# light_clock.net
KiCad netlist of a schematic drawn in Altium Designer
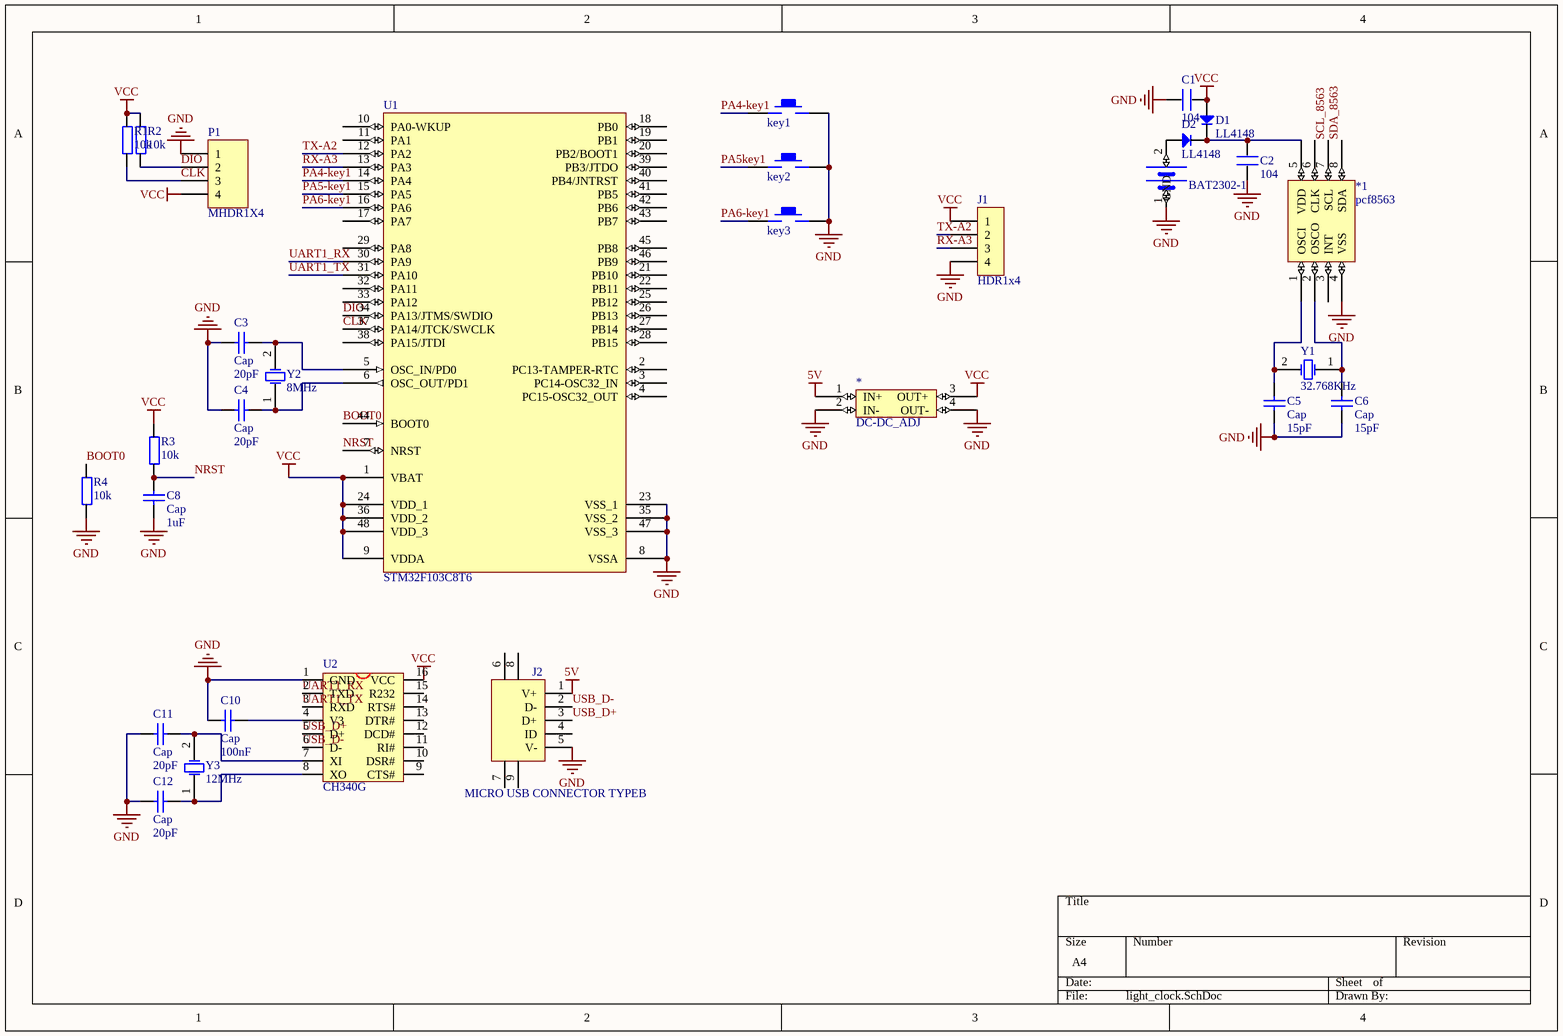
[diagram p0: light_clock.SchDoc]

(export (version "E")
  (design (tool "Eeschema 10.0.6"))
  (components
    (comp (ref "*")
      (value "DC-DC_ADJ")
      (footprint "DC-DC_ADJ")
      (libsource (lib "General") (part "DC-DC_ADJ"))
    )
    (comp (ref "*1") (value "pcf8563") (footprint "SOP-8") (libsource (lib "WARSHIP") (part "pcf8563")))
    (comp (ref "BAT2302-1")
      (value "BAT2302")
      (footprint "CR2302")
      (libsource (lib "WARSHIP") (part "BAT2302"))
    )
    (comp (ref "C1") (value "104") (footprint "0603") (libsource (lib "WARSHIP") (part "C")))
    (comp (ref "C2") (value "104") (footprint "0603") (libsource (lib "WARSHIP") (part "C")))
    (comp (ref "C3")
      (value "Cap")
      (footprint "0603")
      (description "Capacitor")
      (fields (field (name "ALTIUM_VALUE") "20pF") (field (name "PUBLISHER") "Altium Limited"))
      (libsource (lib "Miscellaneous Devices") (part "Cap"))
    )
    (comp (ref "C4")
      (value "Cap")
      (footprint "0603")
      (description "Capacitor")
      (fields (field (name "ALTIUM_VALUE") "20pF") (field (name "PUBLISHER") "Altium Limited"))
      (libsource (lib "Miscellaneous Devices") (part "Cap"))
    )
    (comp (ref "C5")
      (value "Cap")
      (footprint "0603")
      (description "Capacitor")
      (fields (field (name "ALTIUM_VALUE") "15pF") (field (name "PUBLISHER") "Altium Limited"))
      (libsource (lib "Miscellaneous Devices") (part "Cap"))
    )
    (comp (ref "C6")
      (value "Cap")
      (footprint "0603")
      (description "Capacitor")
      (fields (field (name "ALTIUM_VALUE") "15pF") (field (name "PUBLISHER") "Altium Limited"))
      (libsource (lib "Miscellaneous Devices") (part "Cap"))
    )
    (comp (ref "C8")
      (value "Cap")
      (footprint "0603")
      (description "Capacitor")
      (fields (field (name "ALTIUM_VALUE") "1uF") (field (name "PUBLISHER") "Altium Limited"))
      (libsource (lib "Miscellaneous Devices") (part "Cap"))
    )
    (comp (ref "C10")
      (value "Cap")
      (footprint "0603")
      (description "Capacitor")
      (fields (field (name "ALTIUM_VALUE") "100nF") (field (name "PUBLISHER") "Altium Limited"))
      (libsource (lib "Miscellaneous Devices") (part "Cap"))
    )
    (comp (ref "C11")
      (value "Cap")
      (footprint "0603")
      (description "Capacitor")
      (fields (field (name "ALTIUM_VALUE") "20pF") (field (name "PUBLISHER") "Altium Limited"))
      (libsource (lib "Miscellaneous Devices") (part "Cap"))
    )
    (comp (ref "C12")
      (value "Cap")
      (footprint "0603")
      (description "Capacitor")
      (fields (field (name "ALTIUM_VALUE") "20pF") (field (name "PUBLISHER") "Altium Limited"))
      (libsource (lib "Miscellaneous Devices") (part "Cap"))
    )
    (comp (ref "D1") (value "LL4148") (footprint "LL4148") (libsource (lib "WARSHIP") (part "LL4148")))
    (comp (ref "D2") (value "LL4148") (footprint "LL4148") (libsource (lib "WARSHIP") (part "LL4148")))
    (comp (ref "J1")
      (value "HDR1x4")
      (footprint "PIN-4-2.0-0.8")
      (description "Connector")
      (libsource (lib "General") (part "HDR1x4"))
    )
    (comp (ref "J2")
      (value "MICRO USB CONNECTOR TYPEB")
      (footprint "MICRO USB MK5P")
      (description "USB Connector")
      (libsource (lib "General") (part "MICRO USB CONNECTOR TYPEB"))
    )
    (comp (ref "key1") (value "KEY_M") (footprint "KEY_weidong") (libsource (lib "WARSHIP") (part "KEY_M")))
    (comp (ref "key2") (value "KEY_M") (footprint "KEY_weidong") (libsource (lib "WARSHIP") (part "KEY_M")))
    (comp (ref "key3") (value "KEY_M") (footprint "KEY_weidong") (libsource (lib "WARSHIP") (part "KEY_M")))
    (comp (ref "P1")
      (value "MHDR1X4")
      (footprint "HDR1X4")
      (description "Header, 4-Pin")
      (fields (field (name "PUBLISHER") "Altium Limited"))
      (libsource (lib "Miscellaneous Connectors") (part "MHDR1X4"))
    )
    (comp (ref "R1") (value "10k") (footprint "0603") (libsource (lib "WarShip V3 STM32103封装库") (part "R")))
    (comp (ref "R2") (value "10k") (footprint "0603") (libsource (lib "WarShip V3 STM32103封装库") (part "R")))
    (comp (ref "R3") (value "10k") (footprint "0603") (libsource (lib "WarShip V3 STM32103封装库") (part "R")))
    (comp (ref "R4") (value "10k") (footprint "0603") (libsource (lib "WarShip V3 STM32103封装库") (part "R")))
    (comp (ref "U1")
      (value "STM32F103C8T6")
      (footprint "STM-LQFP48_N")
      (description "STM32 ARM-based 32-bit MCU with 64 Kbytes Flash, 48-pin LQFP, Industrial Temperature")
      (fields (field (name "PUBLISHER") "*"))
      (libsource (lib "ST Microcontroller 32-Bit STM32 SCH") (part "STM32F103C8T6"))
    )
    (comp (ref "U2")
      (value "CH340G")
      (footprint "SOP16M")
      (description "USB2UART")
      (libsource (lib "WarShip V3 STM32103封装库") (part "CH340G"))
    )
    (comp (ref "Y1")
      (value "32.768KHz")
      (footprint "PIN-2-2.0-0.8")
      (description "Crystal Oscillator")
      (fields (field (name "PUBLISHER") "Altium Limited"))
      (libsource (lib "WarShip V3 STM32103封装库") (part "XTAL"))
    )
    (comp (ref "Y2")
      (value "8MHz")
      (footprint "XTAL_US")
      (description "Crystal Oscillator")
      (fields (field (name "PUBLISHER") "Altium Limited"))
      (libsource (lib "WarShip V3 STM32103封装库") (part "XTAL"))
    )
    (comp (ref "Y3")
      (value "12MHz")
      (footprint "PIN-2-2.0-0.8")
      (description "Crystal Oscillator")
      (fields (field (name "PUBLISHER") "Altium Limited"))
      (libsource (lib "WarShip V3 STM32103封装库") (part "XTAL"))
    )
  )
  (nets
    (net (code "1") (name "/BOOT0") (class "Default")
      (node (ref "R4") (pin "2") (pintype "passive"))
      (node (ref "U1") (pin "44") (pinfunction "BOOT0_44") (pintype "input"))
    )
    (net (code "2") (name "/CLK") (class "Default")
      (node (ref "P1") (pin "3") (pinfunction "3_3") (pintype "passive"))
      (node (ref "R1") (pin "1") (pintype "passive"))
      (node (ref "U1") (pin "37") (pinfunction "PA14/JTCK/SWCLK_37") (pintype "bidirectional"))
    )
    (net (code "3") (name "/DIO") (class "Default")
      (node (ref "P1") (pin "2") (pinfunction "2_2") (pintype "passive"))
      (node (ref "R2") (pin "1") (pintype "passive"))
      (node (ref "U1") (pin "34") (pinfunction "PA13/JTMS/SWDIO_34") (pintype "bidirectional"))
    )
    (net (code "4") (name "/NRST") (class "Default")
      (node (ref "C8") (pin "2") (pinfunction "2_2") (pintype "passive"))
      (node (ref "R3") (pin "1") (pintype "passive"))
      (node (ref "U1") (pin "7") (pinfunction "NRST_7") (pintype "bidirectional"))
    )
    (net (code "5") (name "/PA4-key1") (class "Default")
      (node (ref "U1") (pin "14") (pinfunction "PA4_14") (pintype "bidirectional"))
      (node (ref "key1") (pin "1") (pinfunction "1_1") (pintype "passive"))
    )
    (net (code "6") (name "/PA5-key1") (class "Default")
      (node (ref "U1") (pin "15") (pinfunction "PA5_15") (pintype "bidirectional"))
    )
    (net (code "7") (name "/PA5key1") (class "Default")
      (node (ref "key2") (pin "1") (pinfunction "1_1") (pintype "passive"))
    )
    (net (code "8") (name "/PA6-key1") (class "Default")
      (node (ref "U1") (pin "16") (pinfunction "PA6_16") (pintype "bidirectional"))
      (node (ref "key3") (pin "1") (pinfunction "1_1") (pintype "passive"))
    )
    (net (code "9") (name "/RX-A3") (class "Default")
      (node (ref "J1") (pin "3") (pinfunction "3_3") (pintype "passive"))
      (node (ref "U1") (pin "13") (pinfunction "PA3_13") (pintype "bidirectional"))
    )
    (net (code "10") (name "/SCL_8563") (class "Default")
      (node (ref "*1") (pin "7") (pinfunction "SCL_7") (pintype "bidirectional"))
    )
    (net (code "11") (name "/SDA_8563") (class "Default")
      (node (ref "*1") (pin "8") (pinfunction "SDA_8") (pintype "bidirectional"))
    )
    (net (code "12") (name "/TX-A2") (class "Default")
      (node (ref "J1") (pin "2") (pinfunction "2_2") (pintype "passive"))
      (node (ref "U1") (pin "12") (pinfunction "PA2_12") (pintype "bidirectional"))
    )
    (net (code "13") (name "/UART1_RX") (class "Default")
      (node (ref "U1") (pin "30") (pinfunction "PA9_30") (pintype "bidirectional"))
      (node (ref "U2") (pin "2") (pinfunction "TXD_2") (pintype "passive"))
    )
    (net (code "14") (name "/UART1_TX") (class "Default")
      (node (ref "U1") (pin "31") (pinfunction "PA10_31") (pintype "bidirectional"))
      (node (ref "U2") (pin "3") (pinfunction "RXD_3") (pintype "passive"))
    )
    (net (code "15") (name "/USB_D+") (class "Default")
      (node (ref "J2") (pin "3") (pinfunction "D+_3") (pintype "passive"))
      (node (ref "U2") (pin "5") (pinfunction "D+_5") (pintype "passive"))
    )
    (net (code "16") (name "/USB_D-") (class "Default")
      (node (ref "J2") (pin "2") (pinfunction "D-_2") (pintype "passive"))
      (node (ref "U2") (pin "6") (pinfunction "D-_6") (pintype "passive"))
    )
    (net (code "17") (name "5V") (class "Default")
      (node (ref "*") (pin "1") (pinfunction "IN+_1") (pintype "bidirectional"))
      (node (ref "J2") (pin "1") (pinfunction "V+_1") (pintype "passive"))
    )
    (net (code "18") (name "GND") (class "Default")
      (node (ref "*") (pin "2") (pinfunction "IN-_2") (pintype "bidirectional"))
      (node (ref "*") (pin "4") (pinfunction "OUT-_4") (pintype "bidirectional"))
      (node (ref "*1") (pin "4") (pinfunction "VSS_4") (pintype "bidirectional"))
      (node (ref "BAT2302-1") (pin "1") (pinfunction "VCC_1") (pintype "bidirectional"))
      (node (ref "C1") (pin "1") (pintype "passive"))
      (node (ref "C10") (pin "2") (pinfunction "2_2") (pintype "passive"))
      (node (ref "C11") (pin "1") (pinfunction "1_1") (pintype "passive"))
      (node (ref "C12") (pin "1") (pinfunction "1_1") (pintype "passive"))
      (node (ref "C2") (pin "1") (pintype "passive"))
      (node (ref "C3") (pin "1") (pinfunction "1_1") (pintype "passive"))
      (node (ref "C4") (pin "1") (pinfunction "1_1") (pintype "passive"))
      (node (ref "C5") (pin "1") (pinfunction "1_1") (pintype "passive"))
      (node (ref "C6") (pin "1") (pinfunction "1_1") (pintype "passive"))
      (node (ref "C8") (pin "1") (pinfunction "1_1") (pintype "passive"))
      (node (ref "J1") (pin "4") (pinfunction "4_4") (pintype "passive"))
      (node (ref "J2") (pin "5") (pinfunction "V-_5") (pintype "passive"))
      (node (ref "P1") (pin "1") (pinfunction "1_1") (pintype "passive"))
      (node (ref "R4") (pin "1") (pintype "passive"))
      (node (ref "U1") (pin "23") (pinfunction "VSS_1_23") (pintype "power_in"))
      (node (ref "U1") (pin "35") (pinfunction "VSS_2_35") (pintype "power_in"))
      (node (ref "U1") (pin "47") (pinfunction "VSS_3_47") (pintype "power_in"))
      (node (ref "U1") (pin "8") (pinfunction "VSSA_8") (pintype "power_in"))
      (node (ref "U2") (pin "1") (pinfunction "GND_1") (pintype "passive"))
      (node (ref "key1") (pin "2") (pinfunction "2_2") (pintype "passive"))
      (node (ref "key2") (pin "2") (pinfunction "2_2") (pintype "passive"))
      (node (ref "key3") (pin "2") (pinfunction "2_2") (pintype "passive"))
    )
    (net (code "19") (name "Net-(*1-OSCI)") (class "Default")
      (node (ref "*1") (pin "1") (pinfunction "OSCI_1") (pintype "bidirectional"))
      (node (ref "C5") (pin "2") (pinfunction "2_2") (pintype "passive"))
      (node (ref "Y1") (pin "2") (pinfunction "OSC2_2") (pintype "passive"))
    )
    (net (code "20") (name "Net-(*1-OSCO)") (class "Default")
      (node (ref "*1") (pin "2") (pinfunction "OSCO_2") (pintype "bidirectional"))
      (node (ref "C6") (pin "2") (pinfunction "2_2") (pintype "passive"))
      (node (ref "Y1") (pin "1") (pinfunction "OSC1_1") (pintype "passive"))
    )
    (net (code "21") (name "Net-(*1-VDD)") (class "Default")
      (node (ref "*1") (pin "5") (pinfunction "VDD_5") (pintype "bidirectional"))
      (node (ref "C2") (pin "2") (pintype "passive"))
      (node (ref "D1") (pin "1") (pintype "passive"))
      (node (ref "D2") (pin "1") (pintype "passive"))
    )
    (net (code "22") (name "Net-(BAT2302-1-GND)") (class "Default")
      (node (ref "BAT2302-1") (pin "2") (pinfunction "GND_2") (pintype "bidirectional"))
      (node (ref "D2") (pin "2") (pintype "passive"))
    )
    (net (code "23") (name "Net-(U1-OSC_IN{slash}PD0)") (class "Default")
      (node (ref "C3") (pin "2") (pinfunction "2_2") (pintype "passive"))
      (node (ref "U1") (pin "5") (pinfunction "OSC_IN/PD0_5") (pintype "input"))
      (node (ref "Y2") (pin "2") (pinfunction "OSC2_2") (pintype "passive"))
    )
    (net (code "24") (name "Net-(U1-OSC_OUT{slash}PD1)") (class "Default")
      (node (ref "C4") (pin "2") (pinfunction "2_2") (pintype "passive"))
      (node (ref "U1") (pin "6") (pinfunction "OSC_OUT/PD1_6") (pintype "output"))
      (node (ref "Y2") (pin "1") (pinfunction "OSC1_1") (pintype "passive"))
    )
    (net (code "25") (name "Net-(U2-V3)") (class "Default")
      (node (ref "C10") (pin "1") (pinfunction "1_1") (pintype "passive"))
      (node (ref "U2") (pin "4") (pinfunction "V3_4") (pintype "passive"))
    )
    (net (code "26") (name "Net-(U2-XI)") (class "Default")
      (node (ref "C11") (pin "2") (pinfunction "2_2") (pintype "passive"))
      (node (ref "U2") (pin "7") (pinfunction "XI_7") (pintype "passive"))
      (node (ref "Y3") (pin "2") (pinfunction "OSC2_2") (pintype "passive"))
    )
    (net (code "27") (name "Net-(U2-XO)") (class "Default")
      (node (ref "C12") (pin "2") (pinfunction "2_2") (pintype "passive"))
      (node (ref "U2") (pin "8") (pinfunction "XO_8") (pintype "passive"))
      (node (ref "Y3") (pin "1") (pinfunction "OSC1_1") (pintype "passive"))
    )
    (net (code "28") (name "VCC") (class "Default")
      (node (ref "*") (pin "3") (pinfunction "OUT+_3") (pintype "bidirectional"))
      (node (ref "C1") (pin "2") (pintype "passive"))
      (node (ref "D1") (pin "2") (pintype "passive"))
      (node (ref "J1") (pin "1") (pinfunction "1_1") (pintype "passive"))
      (node (ref "P1") (pin "4") (pinfunction "4_4") (pintype "passive"))
      (node (ref "R1") (pin "2") (pintype "passive"))
      (node (ref "R2") (pin "2") (pintype "passive"))
      (node (ref "R3") (pin "2") (pintype "passive"))
      (node (ref "U1") (pin "1") (pinfunction "VBAT_1") (pintype "power_in"))
      (node (ref "U1") (pin "24") (pinfunction "VDD_1_24") (pintype "power_in"))
      (node (ref "U1") (pin "36") (pinfunction "VDD_2_36") (pintype "power_in"))
      (node (ref "U1") (pin "48") (pinfunction "VDD_3_48") (pintype "power_in"))
      (node (ref "U1") (pin "9") (pinfunction "VDDA_9") (pintype "power_in"))
      (node (ref "U2") (pin "16") (pinfunction "VCC_16") (pintype "passive"))
    )
    (net (code "29") (name "unconnected-(*1-CLK-Pad6)") (class "Default")
      (node (ref "*1") (pin "6") (pinfunction "CLK_6") (pintype "bidirectional"))
    )
    (net (code "30") (name "unconnected-(*1-INT-Pad3)") (class "Default")
      (node (ref "*1") (pin "3") (pinfunction "INT_3") (pintype "bidirectional"))
    )
    (net (code "31") (name "unconnected-(J2-ID-Pad4)") (class "Default")
      (node (ref "J2") (pin "4") (pinfunction "ID_4") (pintype "passive"))
    )
    (net (code "32") (name "unconnected-(J2-Pad6)") (class "Default")
      (node (ref "J2") (pin "6") (pintype "passive"))
    )
    (net (code "33") (name "unconnected-(J2-Pad7)") (class "Default")
      (node (ref "J2") (pin "7") (pintype "passive"))
    )
    (net (code "34") (name "unconnected-(J2-Pad8)") (class "Default")
      (node (ref "J2") (pin "8") (pintype "passive"))
    )
    (net (code "35") (name "unconnected-(J2-Pad9)") (class "Default")
      (node (ref "J2") (pin "9") (pintype "passive"))
    )
    (net (code "36") (name "unconnected-(U1-PA0-WKUP-Pad10)") (class "Default")
      (node (ref "U1") (pin "10") (pinfunction "PA0-WKUP_10") (pintype "bidirectional"))
    )
    (net (code "37") (name "unconnected-(U1-PA1-Pad11)") (class "Default")
      (node (ref "U1") (pin "11") (pinfunction "PA1_11") (pintype "bidirectional"))
    )
    (net (code "38") (name "unconnected-(U1-PA7-Pad17)") (class "Default")
      (node (ref "U1") (pin "17") (pinfunction "PA7_17") (pintype "bidirectional"))
    )
    (net (code "39") (name "unconnected-(U1-PA8-Pad29)") (class "Default")
      (node (ref "U1") (pin "29") (pinfunction "PA8_29") (pintype "bidirectional"))
    )
    (net (code "40") (name "unconnected-(U1-PA11-Pad32)") (class "Default")
      (node (ref "U1") (pin "32") (pinfunction "PA11_32") (pintype "bidirectional"))
    )
    (net (code "41") (name "unconnected-(U1-PA12-Pad33)") (class "Default")
      (node (ref "U1") (pin "33") (pinfunction "PA12_33") (pintype "bidirectional"))
    )
    (net (code "42") (name "unconnected-(U1-PA15{slash}JTDI-Pad38)") (class "Default")
      (node (ref "U1") (pin "38") (pinfunction "PA15/JTDI_38") (pintype "bidirectional"))
    )
    (net (code "43") (name "unconnected-(U1-PB0-Pad18)") (class "Default")
      (node (ref "U1") (pin "18") (pinfunction "PB0_18") (pintype "bidirectional"))
    )
    (net (code "44") (name "unconnected-(U1-PB1-Pad19)") (class "Default")
      (node (ref "U1") (pin "19") (pinfunction "PB1_19") (pintype "bidirectional"))
    )
    (net (code "45") (name "unconnected-(U1-PB2{slash}BOOT1-Pad20)") (class "Default")
      (node (ref "U1") (pin "20") (pinfunction "PB2/BOOT1_20") (pintype "bidirectional"))
    )
    (net (code "46") (name "unconnected-(U1-PB3{slash}JTDO-Pad39)") (class "Default")
      (node (ref "U1") (pin "39") (pinfunction "PB3/JTDO_39") (pintype "bidirectional"))
    )
    (net (code "47") (name "unconnected-(U1-PB4{slash}JNTRST-Pad40)") (class "Default")
      (node (ref "U1") (pin "40") (pinfunction "PB4/JNTRST_40") (pintype "bidirectional"))
    )
    (net (code "48") (name "unconnected-(U1-PB5-Pad41)") (class "Default")
      (node (ref "U1") (pin "41") (pinfunction "PB5_41") (pintype "bidirectional"))
    )
    (net (code "49") (name "unconnected-(U1-PB6-Pad42)") (class "Default")
      (node (ref "U1") (pin "42") (pinfunction "PB6_42") (pintype "bidirectional"))
    )
    (net (code "50") (name "unconnected-(U1-PB7-Pad43)") (class "Default")
      (node (ref "U1") (pin "43") (pinfunction "PB7_43") (pintype "bidirectional"))
    )
    (net (code "51") (name "unconnected-(U1-PB8-Pad45)") (class "Default")
      (node (ref "U1") (pin "45") (pinfunction "PB8_45") (pintype "bidirectional"))
    )
    (net (code "52") (name "unconnected-(U1-PB9-Pad46)") (class "Default")
      (node (ref "U1") (pin "46") (pinfunction "PB9_46") (pintype "bidirectional"))
    )
    (net (code "53") (name "unconnected-(U1-PB10-Pad21)") (class "Default")
      (node (ref "U1") (pin "21") (pinfunction "PB10_21") (pintype "bidirectional"))
    )
    (net (code "54") (name "unconnected-(U1-PB11-Pad22)") (class "Default")
      (node (ref "U1") (pin "22") (pinfunction "PB11_22") (pintype "bidirectional"))
    )
    (net (code "55") (name "unconnected-(U1-PB12-Pad25)") (class "Default")
      (node (ref "U1") (pin "25") (pinfunction "PB12_25") (pintype "bidirectional"))
    )
    (net (code "56") (name "unconnected-(U1-PB13-Pad26)") (class "Default")
      (node (ref "U1") (pin "26") (pinfunction "PB13_26") (pintype "bidirectional"))
    )
    (net (code "57") (name "unconnected-(U1-PB14-Pad27)") (class "Default")
      (node (ref "U1") (pin "27") (pinfunction "PB14_27") (pintype "bidirectional"))
    )
    (net (code "58") (name "unconnected-(U1-PB15-Pad28)") (class "Default")
      (node (ref "U1") (pin "28") (pinfunction "PB15_28") (pintype "bidirectional"))
    )
    (net (code "59") (name "unconnected-(U1-PC13-TAMPER-RTC-Pad2)") (class "Default")
      (node (ref "U1") (pin "2") (pinfunction "PC13-TAMPER-RTC_2") (pintype "bidirectional"))
    )
    (net (code "60") (name "unconnected-(U1-PC14-OSC32_IN-Pad3)") (class "Default")
      (node (ref "U1") (pin "3") (pinfunction "PC14-OSC32_IN_3") (pintype "bidirectional"))
    )
    (net (code "61") (name "unconnected-(U1-PC15-OSC32_OUT-Pad4)") (class "Default")
      (node (ref "U1") (pin "4") (pinfunction "PC15-OSC32_OUT_4") (pintype "bidirectional"))
    )
    (net (code "62") (name "unconnected-(U2-CTS#-Pad9)") (class "Default")
      (node (ref "U2") (pin "9") (pinfunction "CTS#_9") (pintype "passive"))
    )
    (net (code "63") (name "unconnected-(U2-DCD#-Pad12)") (class "Default")
      (node (ref "U2") (pin "12") (pinfunction "DCD#_12") (pintype "passive"))
    )
    (net (code "64") (name "unconnected-(U2-DSR#-Pad10)") (class "Default")
      (node (ref "U2") (pin "10") (pinfunction "DSR#_10") (pintype "passive"))
    )
    (net (code "65") (name "unconnected-(U2-DTR#-Pad13)") (class "Default")
      (node (ref "U2") (pin "13") (pinfunction "DTR#_13") (pintype "passive"))
    )
    (net (code "66") (name "unconnected-(U2-R232-Pad15)") (class "Default")
      (node (ref "U2") (pin "15") (pinfunction "R232_15") (pintype "passive"))
    )
    (net (code "67") (name "unconnected-(U2-RI#-Pad11)") (class "Default")
      (node (ref "U2") (pin "11") (pinfunction "RI#_11") (pintype "passive"))
    )
    (net (code "68") (name "unconnected-(U2-RTS#-Pad14)") (class "Default")
      (node (ref "U2") (pin "14") (pinfunction "RTS#_14") (pintype "passive"))
    )
  )
)
